# SUBBOARD-current_measurement.net
KiCad netlist of a schematic drawn in Altium Designer
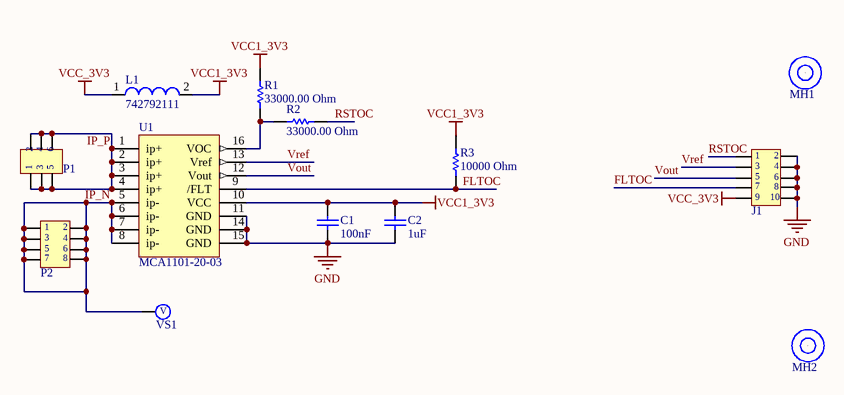
[diagram p0: SUBBOARD-current_measurement.SchDoc]

(export (version "E")
  (design (tool "Eeschema 10.0.6"))
  (components
    (comp (ref "C1")
      (value "100nF")
      (footprint "CAPC0603(1608)100_L")
      (description "CAP 100nF 10V ±10% 0603 (1608 Metric) Thickness 1mm SMD")
      (fields (field (name "TOLERANCE") "Â±10%") (field (name "Comment") "CAP 100nF 10V 0603(1608)"))
      (libsource (lib "Altium Content Vault") (part "CAP"))
    )
    (comp (ref "C2")
      (value "1uF")
      (footprint "CAPC0603(1608)100_L")
      (description "CAP 1uF 50V ±20% 0603 (1608 Metric) Thickness 1mm SMD")
      (fields (field (name "TOLERANCE") "Â±20%") (field (name "Comment") "CAP 1uF 50V 0603(1608)"))
      (libsource (lib "Altium Content Vault") (part "CAP"))
    )
    (comp (ref "J1")
      (value "0878311020")
      (footprint "0878311020")
      (description "Conn Shrouded Header HDR 10 POS 2mm Solder ST Thru-Hole Milli-Grid™ Tube")
      (fields (field (name "MANUFACTURER") "Molex"))
      (libsource (lib "Altium_Library_POWERLAB") (part "0878311020"))
    )
    (comp (ref "L1")
      (value "742792111")
      (footprint "SMD-1206")
      (description "SMD EMI Suppression Ferrite Bead WE-CBF, Z = 26 Ohm")
      (libsource (lib "Altium Content Vault") (part "PAS-IND-INDUCTOR-2"))
    )
    (comp (ref "MH1")
      (value "9774020633R")
      (footprint "9774020633R")
      (fields (field (name "MANUFACTURER") "Wurth Electronics"))
      (libsource (lib "Altium_Library_POWERLAB") (part "9774020633R"))
    )
    (comp (ref "MH2")
      (value "9774020633R")
      (footprint "9774020633R")
      (fields (field (name "MANUFACTURER") "Wurth Electronics"))
      (libsource (lib "Altium_Library_POWERLAB") (part "9774020633R"))
    )
    (comp (ref "P1")
      (value "TSW-103-15-G-D")
      (footprint "TSW-103-15-G-D")
      (description ".025\" SQ. TERMINAL STRIPS")
      (fields (field (name "MANUFACTURER") "Samtec"))
      (libsource (lib "Altium_Library_POWERLAB") (part "TSW-103-15-G-D"))
    )
    (comp (ref "P2")
      (value "TSW-104-15-G-D")
      (footprint "TSW-104-15-G-D")
      (fields (field (name "MANUFACTURER") "Samtec"))
      (libsource (lib "Altium_Library_POWERLAB") (part "TSW-104-15-G-D"))
    )
    (comp (ref "R1")
      (value "33000.00 Ohm")
      (footprint "RESC0805(2012)_N")
      (description "33K 0.125W 5% 0805 (2012 Metric)  SMD")
      (fields (field (name "POWER") "0.125 W") (field (name "TOLERANCE") "5 %"))
      (libsource (lib "Altium Content Vault") (part "RES"))
    )
    (comp (ref "R2")
      (value "33000.00 Ohm")
      (footprint "RESC0805(2012)_M")
      (description "33K 0.125W 5% 0805 (2012 Metric)  SMD")
      (fields (field (name "POWER") "0.125 W") (field (name "TOLERANCE") "5 %"))
      (libsource (lib "Altium Content Vault") (part "RES"))
    )
    (comp (ref "R3")
      (value "10000 Ohm")
      (footprint "RESC1609X50X30NL8T20")
      (description "Chip Resistor, 10 KOhm, +/- 1%, 100 mW, -55 to 155 degC, 0603 (1608 Metric), RoHS, Tape and Reel")
      (fields
        (field (name "MANUFACTURER") "Vishay Semiconductor")
        (field (name "Comment") "CRCW060310K0FKEA")
      )
      (libsource (lib "Altium Content Vault") (part "RES-2"))
    )
    (comp (ref "U1")
      (value "MCA1101-20-03")
      (footprint "SOIC127P1030X265-16N")
      (description "High Accuracy Current Sensor IC with 1.5MHz 3dB Bandwidth and Isolation ±20A,, 3.3V, Ratiometric")
      (fields (field (name "MANUFACTURER") "ACEINNA") (field (name "MOUSER PART NUMBER") "438-MCA1101-20-3"))
      (libsource (lib "Altium_Library_POWERLAB") (part "MCA1101-20-03"))
    )
    (comp (ref "VS1")
      (value "Voltage_Probe")
      (footprint "Voltage Probe")
      (libsource (lib "Altium_Library_POWERLAB") (part "Voltage_Probe"))
    )
  )
  (nets
    (net (code "1") (name "/FLTOC") (class "Default")
      (node (ref "J1") (pin "7") (pinfunction "7_7") (pintype "passive"))
      (node (ref "R3") (pin "2") (pinfunction "2_2") (pintype "passive"))
      (node (ref "U1") (pin "9") (pinfunction "/FLT_9") (pintype "open_collector"))
    )
    (net (code "2") (name "/IP_N") (class "Default")
      (node (ref "P2") (pin "1") (pinfunction "1_1") (pintype "passive"))
      (node (ref "P2") (pin "2") (pinfunction "2_2") (pintype "passive"))
      (node (ref "P2") (pin "3") (pinfunction "3_3") (pintype "passive"))
      (node (ref "P2") (pin "4") (pinfunction "4_4") (pintype "passive"))
      (node (ref "P2") (pin "5") (pinfunction "5_5") (pintype "passive"))
      (node (ref "P2") (pin "6") (pinfunction "6_6") (pintype "passive"))
      (node (ref "P2") (pin "7") (pinfunction "7_7") (pintype "passive"))
      (node (ref "P2") (pin "8") (pinfunction "8_8") (pintype "passive"))
      (node (ref "U1") (pin "5") (pinfunction "ip-_5") (pintype "passive"))
      (node (ref "U1") (pin "6") (pinfunction "ip-_6") (pintype "passive"))
      (node (ref "U1") (pin "7") (pinfunction "ip-_7") (pintype "passive"))
      (node (ref "U1") (pin "8") (pinfunction "ip-_8") (pintype "passive"))
      (node (ref "VS1") (pin "1") (pinfunction "1_1") (pintype "passive"))
    )
    (net (code "3") (name "/IP_P") (class "Default")
      (node (ref "P1") (pin "1") (pinfunction "1_1") (pintype "passive"))
      (node (ref "P1") (pin "2") (pinfunction "2_2") (pintype "passive"))
      (node (ref "P1") (pin "3") (pinfunction "3_3") (pintype "passive"))
      (node (ref "P1") (pin "4") (pinfunction "4_4") (pintype "passive"))
      (node (ref "P1") (pin "5") (pinfunction "5_5") (pintype "passive"))
      (node (ref "P1") (pin "6") (pinfunction "6_6") (pintype "passive"))
      (node (ref "U1") (pin "1") (pinfunction "ip+_1") (pintype "passive"))
      (node (ref "U1") (pin "2") (pinfunction "ip+_2") (pintype "passive"))
      (node (ref "U1") (pin "3") (pinfunction "ip+_3") (pintype "passive"))
      (node (ref "U1") (pin "4") (pinfunction "ip+_4") (pintype "passive"))
    )
    (net (code "4") (name "/RSTOC") (class "Default")
      (node (ref "J1") (pin "1") (pinfunction "1_1") (pintype "passive"))
      (node (ref "R2") (pin "1") (pinfunction "1_1") (pintype "passive"))
    )
    (net (code "5") (name "/Vout") (class "Default")
      (node (ref "J1") (pin "5") (pinfunction "5_5") (pintype "passive"))
      (node (ref "U1") (pin "12") (pinfunction "Vout_12") (pintype "output"))
    )
    (net (code "6") (name "/Vref") (class "Default")
      (node (ref "J1") (pin "3") (pinfunction "3_3") (pintype "passive"))
      (node (ref "U1") (pin "13") (pinfunction "Vref_13") (pintype "output"))
    )
    (net (code "7") (name "GND") (class "Default")
      (node (ref "C1") (pin "1") (pinfunction "1_1") (pintype "passive"))
      (node (ref "C2") (pin "1") (pinfunction "1_1") (pintype "passive"))
      (node (ref "J1") (pin "10") (pinfunction "10_10") (pintype "passive"))
      (node (ref "J1") (pin "2") (pinfunction "2_2") (pintype "passive"))
      (node (ref "J1") (pin "4") (pinfunction "4_4") (pintype "passive"))
      (node (ref "J1") (pin "6") (pinfunction "6_6") (pintype "passive"))
      (node (ref "J1") (pin "8") (pinfunction "8_8") (pintype "passive"))
      (node (ref "U1") (pin "11") (pinfunction "GND_11") (pintype "power_in"))
      (node (ref "U1") (pin "14") (pinfunction "GND_14") (pintype "power_in"))
      (node (ref "U1") (pin "15") (pinfunction "GND_15") (pintype "power_in"))
    )
    (net (code "8") (name "Net-(U1-VOC)") (class "Default")
      (node (ref "R1") (pin "1") (pinfunction "1_1") (pintype "passive"))
      (node (ref "R2") (pin "2") (pinfunction "2_2") (pintype "passive"))
      (node (ref "U1") (pin "16") (pinfunction "VOC_16") (pintype "output"))
    )
    (net (code "9") (name "VCC1_3V3") (class "Default")
      (node (ref "C1") (pin "2") (pinfunction "2_2") (pintype "passive"))
      (node (ref "C2") (pin "2") (pinfunction "2_2") (pintype "passive"))
      (node (ref "L1") (pin "2") (pinfunction "2_2") (pintype "passive"))
      (node (ref "R1") (pin "2") (pinfunction "2_2") (pintype "passive"))
      (node (ref "R3") (pin "1") (pinfunction "1_1") (pintype "passive"))
      (node (ref "U1") (pin "10") (pinfunction "VCC_10") (pintype "power_in"))
    )
    (net (code "10") (name "VCC_3V3") (class "Default")
      (node (ref "J1") (pin "9") (pinfunction "9_9") (pintype "passive"))
      (node (ref "L1") (pin "1") (pinfunction "1_1") (pintype "passive"))
    )
    (net (code "11") (name "unconnected-(MH1-Pad1)") (class "Default")
      (node (ref "MH1") (pin "1") (pinfunction "1_1") (pintype "passive"))
    )
    (net (code "12") (name "unconnected-(MH2-Pad1)") (class "Default")
      (node (ref "MH2") (pin "1") (pinfunction "1_1") (pintype "passive"))
    )
  )
)
